# nunchuck_mod.net
KiCad netlist of a schematic drawn in EAGLE
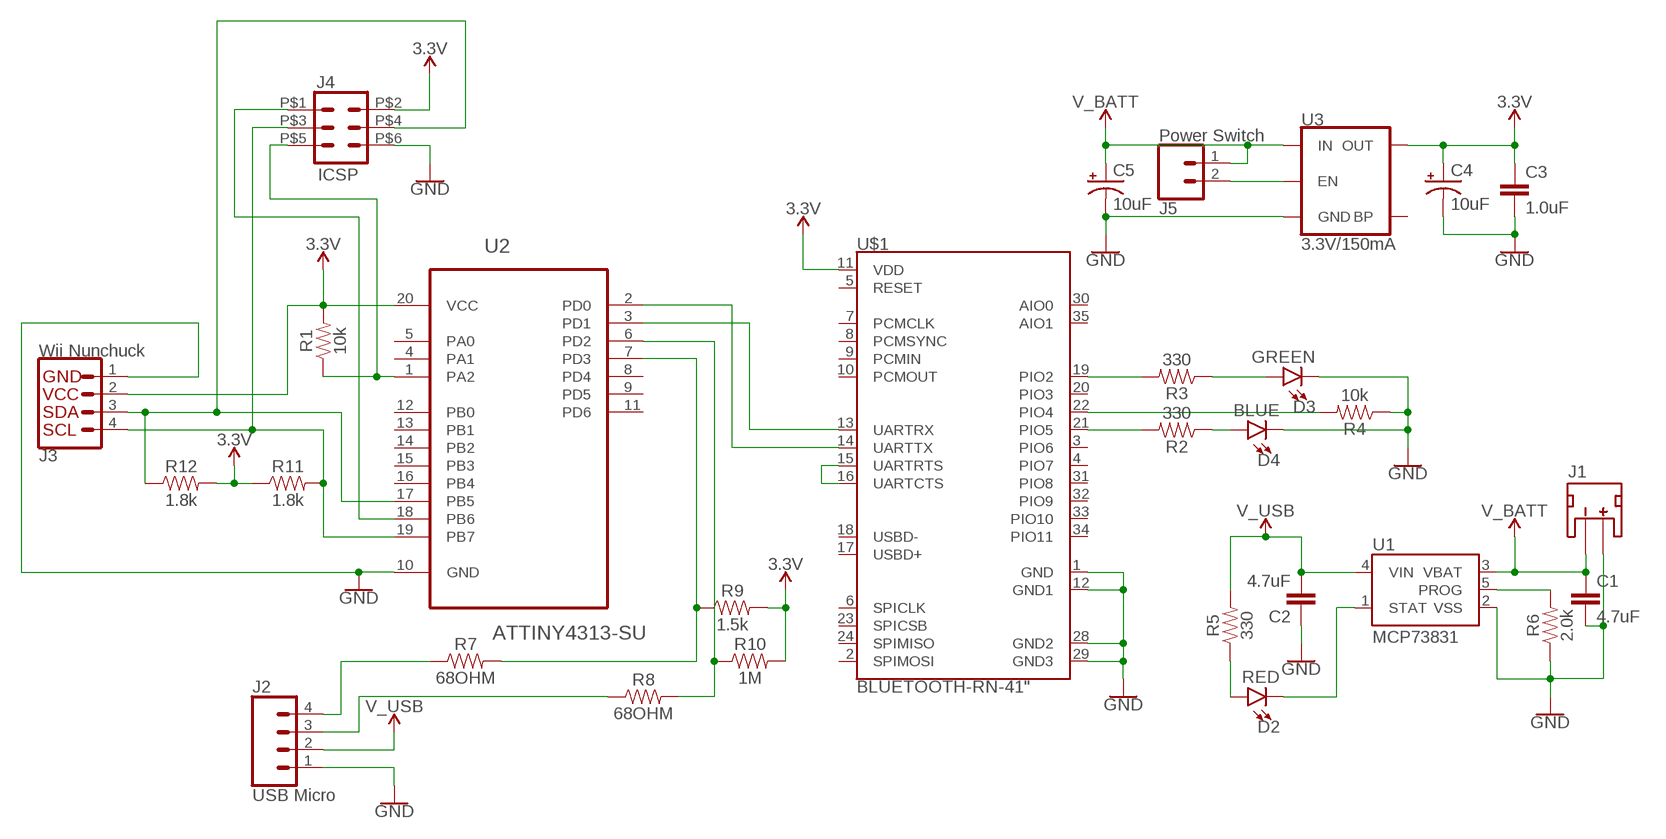
[diagram p0: schematic, sheet 1]

(export (version "E")
  (design (tool "Eeschema 10.0.6"))
  (components
    (comp (ref "C1")
      (value "4.7uF")
      (footprint "eagle-import:0603")
      (libsource (lib "eagle-import") (part "4.7UF0603"))
    )
    (comp (ref "C2")
      (value "4.7uF")
      (footprint "eagle-import:0603")
      (libsource (lib "eagle-import") (part "4.7UF0603"))
    )
    (comp (ref "C3")
      (value "1.0uF")
      (footprint "eagle-import:0603")
      (libsource (lib "eagle-import") (part "1.0UF-0603-16V-10%"))
    )
    (comp (ref "C4")
      (value "10uF")
      (footprint "eagle-import:0603-POLAR")
      (libsource (lib "eagle-import") (part "10UF-POLAR-0603-6.3V-20%(TANT)"))
    )
    (comp (ref "C5")
      (value "10uF")
      (footprint "eagle-import:0603-POLAR")
      (libsource (lib "eagle-import") (part "10UF-POLAR-0603-6.3V-20%(TANT)"))
    )
    (comp (ref "D2")
      (value "RED")
      (footprint "eagle-import:LED-0603")
      (libsource (lib "eagle-import") (part "LED-RED0603"))
    )
    (comp (ref "D3")
      (value "GREEN")
      (footprint "eagle-import:LED-0603")
      (libsource (lib "eagle-import") (part "LED-GREEN0603"))
    )
    (comp (ref "D4")
      (value "BLUE")
      (footprint "eagle-import:LED-0603")
      (libsource (lib "eagle-import") (part "LED-BLUE0603"))
    )
    (comp (ref "J1")
      (value "JST_2MM_MALE")
      (footprint "eagle-import:JST-2-SMD")
      (libsource (lib "eagle-import") (part "JST_2MM_MALE"))
    )
    (comp (ref "J2")
      (value "USB Micro")
      (footprint "eagle-import:1X04")
      (libsource (lib "eagle-import") (part "CONN_04"))
    )
    (comp (ref "J3")
      (value "Wii Nunchuck")
      (footprint "eagle-import:1X04")
      (libsource (lib "eagle-import") (part "I2C_STANDARD"))
    )
    (comp (ref "J4")
      (value "ICSP")
      (footprint "eagle-import:2X3_POGO")
      (libsource (lib "eagle-import") (part "CONN_03X2POGO_PINS"))
    )
    (comp (ref "J5")
      (value "Power Switch")
      (footprint "eagle-import:1X02")
      (libsource (lib "eagle-import") (part "CONN_02"))
    )
    (comp (ref "R1")
      (value "10k")
      (footprint "eagle-import:0603")
      (libsource (lib "eagle-import") (part "10KOHM-0603-1/10W-1%"))
    )
    (comp (ref "R2")
      (value "330")
      (footprint "eagle-import:0603")
      (libsource (lib "eagle-import") (part "330OHM-0603-1/10W-1%"))
    )
    (comp (ref "R3")
      (value "330")
      (footprint "eagle-import:0603")
      (libsource (lib "eagle-import") (part "330OHM-0603-1/10W-1%"))
    )
    (comp (ref "R4")
      (value "10k")
      (footprint "eagle-import:0603")
      (libsource (lib "eagle-import") (part "10KOHM-0603-1/10W-1%"))
    )
    (comp (ref "R5")
      (value "330")
      (footprint "eagle-import:0603")
      (libsource (lib "eagle-import") (part "330OHM-0603-1/10W-1%"))
    )
    (comp (ref "R6")
      (value "2.0k")
      (footprint "eagle-import:0603")
      (libsource (lib "eagle-import") (part "2.0KOHM-0603-1/10W-5%"))
    )
    (comp (ref "R7")
      (value "68OHM")
      (footprint "eagle-import:0603")
      (libsource (lib "eagle-import") (part "68OHM-0603-1/10W-1%"))
    )
    (comp (ref "R8")
      (value "68OHM")
      (footprint "eagle-import:0603")
      (libsource (lib "eagle-import") (part "68OHM-0603-1/10W-1%"))
    )
    (comp (ref "R9")
      (value "1.5k")
      (footprint "eagle-import:0603")
      (libsource (lib "eagle-import") (part "1.5KOHM-0603-1/10W-1%"))
    )
    (comp (ref "R10")
      (value "1M")
      (footprint "eagle-import:0603")
      (libsource (lib "eagle-import") (part "1MOHM-0603-1/4W-5%"))
    )
    (comp (ref "R11")
      (value "1.8k")
      (footprint "eagle-import:0603")
      (libsource (lib "eagle-import") (part "1.8KOHM-0603-1/10W-1%"))
    )
    (comp (ref "R12")
      (value "1.8k")
      (footprint "eagle-import:0603")
      (libsource (lib "eagle-import") (part "1.8KOHM-0603-1/10W-1%"))
    )
    (comp (ref "U$1")
      (value "BLUETOOTH-RN-41\"")
      (footprint "eagle-import:RN41")
      (libsource (lib "eagle-import") (part "BLUETOOTH-RN-41{dblquote}"))
    )
    (comp (ref "U1")
      (value "MCP73831")
      (footprint "eagle-import:SOT23-5")
      (libsource (lib "eagle-import") (part "MCP73831"))
    )
    (comp (ref "U2")
      (value "ATTINY4313-SU")
      (footprint "eagle-import:SOIC127P1032X265-20N")
      (libsource (lib "eagle-import") (part "ATTINY4313-SU"))
    )
    (comp (ref "U3")
      (value "3.3V/150mA")
      (footprint "eagle-import:SOT23-5")
      (libsource (lib "eagle-import") (part "V_REG_MIC52053.3V"))
    )
  )
  (nets
    (net (code "1") (name "3.3V") (class "Default")
      (node (ref "C3") (pin "1") (pinfunction "1_1") (pintype "passive"))
      (node (ref "C4") (pin "+") (pinfunction "+_+") (pintype "passive"))
      (node (ref "J3") (pin "2") (pinfunction "2_2") (pintype "power_in"))
      (node (ref "J4") (pin "P$2") (pinfunction "2_P$2") (pintype "bidirectional"))
      (node (ref "R1") (pin "2") (pinfunction "2_2") (pintype "passive"))
      (node (ref "R10") (pin "2") (pinfunction "2_2") (pintype "passive"))
      (node (ref "R11") (pin "1") (pinfunction "1_1") (pintype "passive"))
      (node (ref "R12") (pin "2") (pinfunction "2_2") (pintype "passive"))
      (node (ref "R9") (pin "2") (pinfunction "2_2") (pintype "passive"))
      (node (ref "U$1") (pin "11") (pinfunction "VDD_11") (pintype "bidirectional"))
      (node (ref "U2") (pin "20") (pinfunction "VCC_20") (pintype "power_in"))
      (node (ref "U3") (pin "5") (pinfunction "OUT_5") (pintype "passive"))
    )
    (net (code "2") (name "GND") (class "Default")
      (node (ref "C1") (pin "2") (pinfunction "2_2") (pintype "passive"))
      (node (ref "C2") (pin "1") (pinfunction "1_1") (pintype "passive"))
      (node (ref "C3") (pin "2") (pinfunction "2_2") (pintype "passive"))
      (node (ref "C4") (pin "-") (pinfunction "-_-") (pintype "passive"))
      (node (ref "C5") (pin "-") (pinfunction "-_-") (pintype "passive"))
      (node (ref "D3") (pin "C") (pinfunction "C_C") (pintype "passive"))
      (node (ref "D4") (pin "C") (pinfunction "C_C") (pintype "passive"))
      (node (ref "J1") (pin "2") (pinfunction "+_2") (pintype "bidirectional"))
      (node (ref "J2") (pin "1") (pinfunction "1_1") (pintype "passive"))
      (node (ref "J3") (pin "1") (pinfunction "1_1") (pintype "power_in"))
      (node (ref "J4") (pin "P$6") (pinfunction "6_P$6") (pintype "bidirectional"))
      (node (ref "R4") (pin "1") (pinfunction "1_1") (pintype "passive"))
      (node (ref "R6") (pin "1") (pinfunction "1_1") (pintype "passive"))
      (node (ref "U$1") (pin "1") (pinfunction "GND_1") (pintype "bidirectional"))
      (node (ref "U$1") (pin "12") (pinfunction "GND1_12") (pintype "bidirectional"))
      (node (ref "U$1") (pin "28") (pinfunction "GND2_28") (pintype "bidirectional"))
      (node (ref "U$1") (pin "29") (pinfunction "GND3_29") (pintype "bidirectional"))
      (node (ref "U1") (pin "2") (pinfunction "VSS_2") (pintype "power_in"))
      (node (ref "U2") (pin "10") (pinfunction "GND_10") (pintype "passive"))
      (node (ref "U3") (pin "2") (pinfunction "GND_2") (pintype "input"))
    )
    (net (code "3") (name "Net-(D2-PadA)") (class "Default")
      (node (ref "D2") (pin "A") (pinfunction "A_A") (pintype "passive"))
      (node (ref "R5") (pin "1") (pinfunction "1_1") (pintype "passive"))
    )
    (net (code "4") (name "Net-(D3-PadA)") (class "Default")
      (node (ref "D3") (pin "A") (pinfunction "A_A") (pintype "passive"))
      (node (ref "R3") (pin "1") (pinfunction "1_1") (pintype "passive"))
    )
    (net (code "5") (name "Net-(D4-PadA)") (class "Default")
      (node (ref "D4") (pin "A") (pinfunction "A_A") (pintype "passive"))
      (node (ref "R2") (pin "1") (pinfunction "1_1") (pintype "passive"))
    )
    (net (code "6") (name "Net-(J2-Pad3)") (class "Default")
      (node (ref "J2") (pin "3") (pinfunction "3_3") (pintype "passive"))
      (node (ref "R8") (pin "1") (pinfunction "1_1") (pintype "passive"))
    )
    (net (code "7") (name "Net-(J2-Pad4)") (class "Default")
      (node (ref "J2") (pin "4") (pinfunction "4_4") (pintype "passive"))
      (node (ref "R7") (pin "1") (pinfunction "1_1") (pintype "passive"))
    )
    (net (code "8") (name "Net-(J4-1)") (class "Default")
      (node (ref "J4") (pin "P$1") (pinfunction "1_P$1") (pintype "bidirectional"))
      (node (ref "U2") (pin "18") (pinfunction "PB6_18") (pintype "bidirectional"))
    )
    (net (code "9") (name "Net-(J4-3)") (class "Default")
      (node (ref "J3") (pin "4") (pinfunction "4_4") (pintype "passive"))
      (node (ref "J4") (pin "P$3") (pinfunction "3_P$3") (pintype "bidirectional"))
      (node (ref "R11") (pin "2") (pinfunction "2_2") (pintype "passive"))
      (node (ref "U2") (pin "19") (pinfunction "PB7_19") (pintype "bidirectional"))
    )
    (net (code "10") (name "Net-(J4-4)") (class "Default")
      (node (ref "J3") (pin "3") (pinfunction "3_3") (pintype "passive"))
      (node (ref "J4") (pin "P$4") (pinfunction "4_P$4") (pintype "bidirectional"))
      (node (ref "R12") (pin "1") (pinfunction "1_1") (pintype "passive"))
      (node (ref "U2") (pin "17") (pinfunction "PB5_17") (pintype "bidirectional"))
    )
    (net (code "11") (name "Net-(J4-5)") (class "Default")
      (node (ref "J4") (pin "P$5") (pinfunction "5_P$5") (pintype "bidirectional"))
      (node (ref "R1") (pin "1") (pinfunction "1_1") (pintype "passive"))
      (node (ref "U2") (pin "1") (pinfunction "PA2_1") (pintype "bidirectional"))
    )
    (net (code "12") (name "Net-(U$1-PIO2)") (class "Default")
      (node (ref "R3") (pin "2") (pinfunction "2_2") (pintype "passive"))
      (node (ref "U$1") (pin "19") (pinfunction "PIO2_19") (pintype "bidirectional"))
    )
    (net (code "13") (name "Net-(U$1-PIO4)") (class "Default")
      (node (ref "R4") (pin "2") (pinfunction "2_2") (pintype "passive"))
      (node (ref "U$1") (pin "22") (pinfunction "PIO4_22") (pintype "bidirectional"))
    )
    (net (code "14") (name "Net-(U$1-PIO5)") (class "Default")
      (node (ref "R2") (pin "2") (pinfunction "2_2") (pintype "passive"))
      (node (ref "U$1") (pin "21") (pinfunction "PIO5_21") (pintype "bidirectional"))
    )
    (net (code "15") (name "Net-(U$1-UARTCTS)") (class "Default")
      (node (ref "U$1") (pin "15") (pinfunction "UARTRTS_15") (pintype "bidirectional"))
      (node (ref "U$1") (pin "16") (pinfunction "UARTCTS_16") (pintype "bidirectional"))
    )
    (net (code "16") (name "Net-(U$1-UARTRX)") (class "Default")
      (node (ref "U$1") (pin "13") (pinfunction "UARTRX_13") (pintype "bidirectional"))
      (node (ref "U2") (pin "3") (pinfunction "PD1_3") (pintype "bidirectional"))
    )
    (net (code "17") (name "Net-(U$1-UARTTX)") (class "Default")
      (node (ref "U$1") (pin "14") (pinfunction "UARTTX_14") (pintype "bidirectional"))
      (node (ref "U2") (pin "2") (pinfunction "PD0_2") (pintype "bidirectional"))
    )
    (net (code "18") (name "Net-(U1-PROG)") (class "Default")
      (node (ref "R6") (pin "2") (pinfunction "2_2") (pintype "passive"))
      (node (ref "U1") (pin "5") (pinfunction "PROG_5") (pintype "input"))
    )
    (net (code "19") (name "Net-(U1-STAT)") (class "Default")
      (node (ref "D2") (pin "C") (pinfunction "C_C") (pintype "passive"))
      (node (ref "U1") (pin "1") (pinfunction "STAT_1") (pintype "output"))
    )
    (net (code "20") (name "Net-(U2-PD2)") (class "Default")
      (node (ref "R10") (pin "1") (pinfunction "1_1") (pintype "passive"))
      (node (ref "R8") (pin "2") (pinfunction "2_2") (pintype "passive"))
      (node (ref "U2") (pin "6") (pinfunction "PD2_6") (pintype "bidirectional"))
    )
    (net (code "21") (name "Net-(U2-PD3)") (class "Default")
      (node (ref "R7") (pin "2") (pinfunction "2_2") (pintype "passive"))
      (node (ref "R9") (pin "1") (pinfunction "1_1") (pintype "passive"))
      (node (ref "U2") (pin "7") (pinfunction "PD3_7") (pintype "bidirectional"))
    )
    (net (code "22") (name "Net-(U3-EN)") (class "Default")
      (node (ref "J5") (pin "2") (pinfunction "2_2") (pintype "passive"))
      (node (ref "U3") (pin "3") (pinfunction "EN_3") (pintype "input"))
    )
    (net (code "23") (name "V_BATT") (class "Default")
      (node (ref "C1") (pin "1") (pinfunction "1_1") (pintype "passive"))
      (node (ref "C5") (pin "+") (pinfunction "+_+") (pintype "passive"))
      (node (ref "J1") (pin "1") (pinfunction "-_1") (pintype "bidirectional"))
      (node (ref "J5") (pin "1") (pinfunction "1_1") (pintype "passive"))
      (node (ref "U1") (pin "3") (pinfunction "VBAT_3") (pintype "power_in"))
      (node (ref "U3") (pin "1") (pinfunction "IN_1") (pintype "input"))
    )
    (net (code "24") (name "V_USB") (class "Default")
      (node (ref "C2") (pin "2") (pinfunction "2_2") (pintype "passive"))
      (node (ref "J2") (pin "2") (pinfunction "2_2") (pintype "passive"))
      (node (ref "R5") (pin "2") (pinfunction "2_2") (pintype "passive"))
      (node (ref "U1") (pin "4") (pinfunction "VIN_4") (pintype "power_in"))
    )
    (net (code "25") (name "unconnected-(J1-PAD1-PadNC1)") (class "Default")
      (node (ref "J1") (pin "NC1") (pinfunction "PAD1_NC1") (pintype "bidirectional"))
    )
    (net (code "26") (name "unconnected-(J1-PAD2-PadNC2)") (class "Default")
      (node (ref "J1") (pin "NC2") (pinfunction "PAD2_NC2") (pintype "bidirectional"))
    )
    (net (code "27") (name "unconnected-(U$1-AIO0-Pad30)") (class "Default")
      (node (ref "U$1") (pin "30") (pinfunction "AIO0_30") (pintype "bidirectional"))
    )
    (net (code "28") (name "unconnected-(U$1-AIO1-Pad35)") (class "Default")
      (node (ref "U$1") (pin "35") (pinfunction "AIO1_35") (pintype "bidirectional"))
    )
    (net (code "29") (name "unconnected-(U$1-PCMCLK-Pad7)") (class "Default")
      (node (ref "U$1") (pin "7") (pinfunction "PCMCLK_7") (pintype "bidirectional"))
    )
    (net (code "30") (name "unconnected-(U$1-PCMIN-Pad9)") (class "Default")
      (node (ref "U$1") (pin "9") (pinfunction "PCMIN_9") (pintype "bidirectional"))
    )
    (net (code "31") (name "unconnected-(U$1-PCMOUT-Pad10)") (class "Default")
      (node (ref "U$1") (pin "10") (pinfunction "PCMOUT_10") (pintype "bidirectional"))
    )
    (net (code "32") (name "unconnected-(U$1-PCMSYNC-Pad8)") (class "Default")
      (node (ref "U$1") (pin "8") (pinfunction "PCMSYNC_8") (pintype "bidirectional"))
    )
    (net (code "33") (name "unconnected-(U$1-PIO3-Pad20)") (class "Default")
      (node (ref "U$1") (pin "20") (pinfunction "PIO3_20") (pintype "bidirectional"))
    )
    (net (code "34") (name "unconnected-(U$1-PIO6-Pad3)") (class "Default")
      (node (ref "U$1") (pin "3") (pinfunction "PIO6_3") (pintype "bidirectional"))
    )
    (net (code "35") (name "unconnected-(U$1-PIO7-Pad4)") (class "Default")
      (node (ref "U$1") (pin "4") (pinfunction "PIO7_4") (pintype "bidirectional"))
    )
    (net (code "36") (name "unconnected-(U$1-PIO8-Pad31)") (class "Default")
      (node (ref "U$1") (pin "31") (pinfunction "PIO8_31") (pintype "bidirectional"))
    )
    (net (code "37") (name "unconnected-(U$1-PIO9-Pad32)") (class "Default")
      (node (ref "U$1") (pin "32") (pinfunction "PIO9_32") (pintype "bidirectional"))
    )
    (net (code "38") (name "unconnected-(U$1-PIO10-Pad33)") (class "Default")
      (node (ref "U$1") (pin "33") (pinfunction "PIO10_33") (pintype "bidirectional"))
    )
    (net (code "39") (name "unconnected-(U$1-PIO11-Pad34)") (class "Default")
      (node (ref "U$1") (pin "34") (pinfunction "PIO11_34") (pintype "bidirectional"))
    )
    (net (code "40") (name "unconnected-(U$1-RESET-Pad5)") (class "Default")
      (node (ref "U$1") (pin "5") (pinfunction "RESET_5") (pintype "bidirectional"))
    )
    (net (code "41") (name "unconnected-(U$1-SPICLK-Pad6)") (class "Default")
      (node (ref "U$1") (pin "6") (pinfunction "SPICLK_6") (pintype "bidirectional"))
    )
    (net (code "42") (name "unconnected-(U$1-SPICSB-Pad23)") (class "Default")
      (node (ref "U$1") (pin "23") (pinfunction "SPICSB_23") (pintype "bidirectional"))
    )
    (net (code "43") (name "unconnected-(U$1-SPIMISO-Pad24)") (class "Default")
      (node (ref "U$1") (pin "24") (pinfunction "SPIMISO_24") (pintype "bidirectional"))
    )
    (net (code "44") (name "unconnected-(U$1-SPIMOSI-Pad2)") (class "Default")
      (node (ref "U$1") (pin "2") (pinfunction "SPIMOSI_2") (pintype "bidirectional"))
    )
    (net (code "45") (name "unconnected-(U$1-USBD+-Pad17)") (class "Default")
      (node (ref "U$1") (pin "17") (pinfunction "USBD+_17") (pintype "bidirectional"))
    )
    (net (code "46") (name "unconnected-(U$1-USBD--Pad18)") (class "Default")
      (node (ref "U$1") (pin "18") (pinfunction "USBD-_18") (pintype "bidirectional"))
    )
    (net (code "47") (name "unconnected-(U2-PA0-Pad5)") (class "Default")
      (node (ref "U2") (pin "5") (pinfunction "PA0_5") (pintype "bidirectional"))
    )
    (net (code "48") (name "unconnected-(U2-PA1-Pad4)") (class "Default")
      (node (ref "U2") (pin "4") (pinfunction "PA1_4") (pintype "bidirectional"))
    )
    (net (code "49") (name "unconnected-(U2-PB0-Pad12)") (class "Default")
      (node (ref "U2") (pin "12") (pinfunction "PB0_12") (pintype "bidirectional"))
    )
    (net (code "50") (name "unconnected-(U2-PB1-Pad13)") (class "Default")
      (node (ref "U2") (pin "13") (pinfunction "PB1_13") (pintype "bidirectional"))
    )
    (net (code "51") (name "unconnected-(U2-PB2-Pad14)") (class "Default")
      (node (ref "U2") (pin "14") (pinfunction "PB2_14") (pintype "bidirectional"))
    )
    (net (code "52") (name "unconnected-(U2-PB3-Pad15)") (class "Default")
      (node (ref "U2") (pin "15") (pinfunction "PB3_15") (pintype "bidirectional"))
    )
    (net (code "53") (name "unconnected-(U2-PB4-Pad16)") (class "Default")
      (node (ref "U2") (pin "16") (pinfunction "PB4_16") (pintype "bidirectional"))
    )
    (net (code "54") (name "unconnected-(U2-PD4-Pad8)") (class "Default")
      (node (ref "U2") (pin "8") (pinfunction "PD4_8") (pintype "bidirectional"))
    )
    (net (code "55") (name "unconnected-(U2-PD5-Pad9)") (class "Default")
      (node (ref "U2") (pin "9") (pinfunction "PD5_9") (pintype "bidirectional"))
    )
    (net (code "56") (name "unconnected-(U2-PD6-Pad11)") (class "Default")
      (node (ref "U2") (pin "11") (pinfunction "PD6_11") (pintype "bidirectional"))
    )
    (net (code "57") (name "unconnected-(U3-BP-Pad4)") (class "Default")
      (node (ref "U3") (pin "4") (pinfunction "BP_4") (pintype "input"))
    )
  )
)
